# Interface.net
KiCad netlist of a schematic drawn in Altium Designer
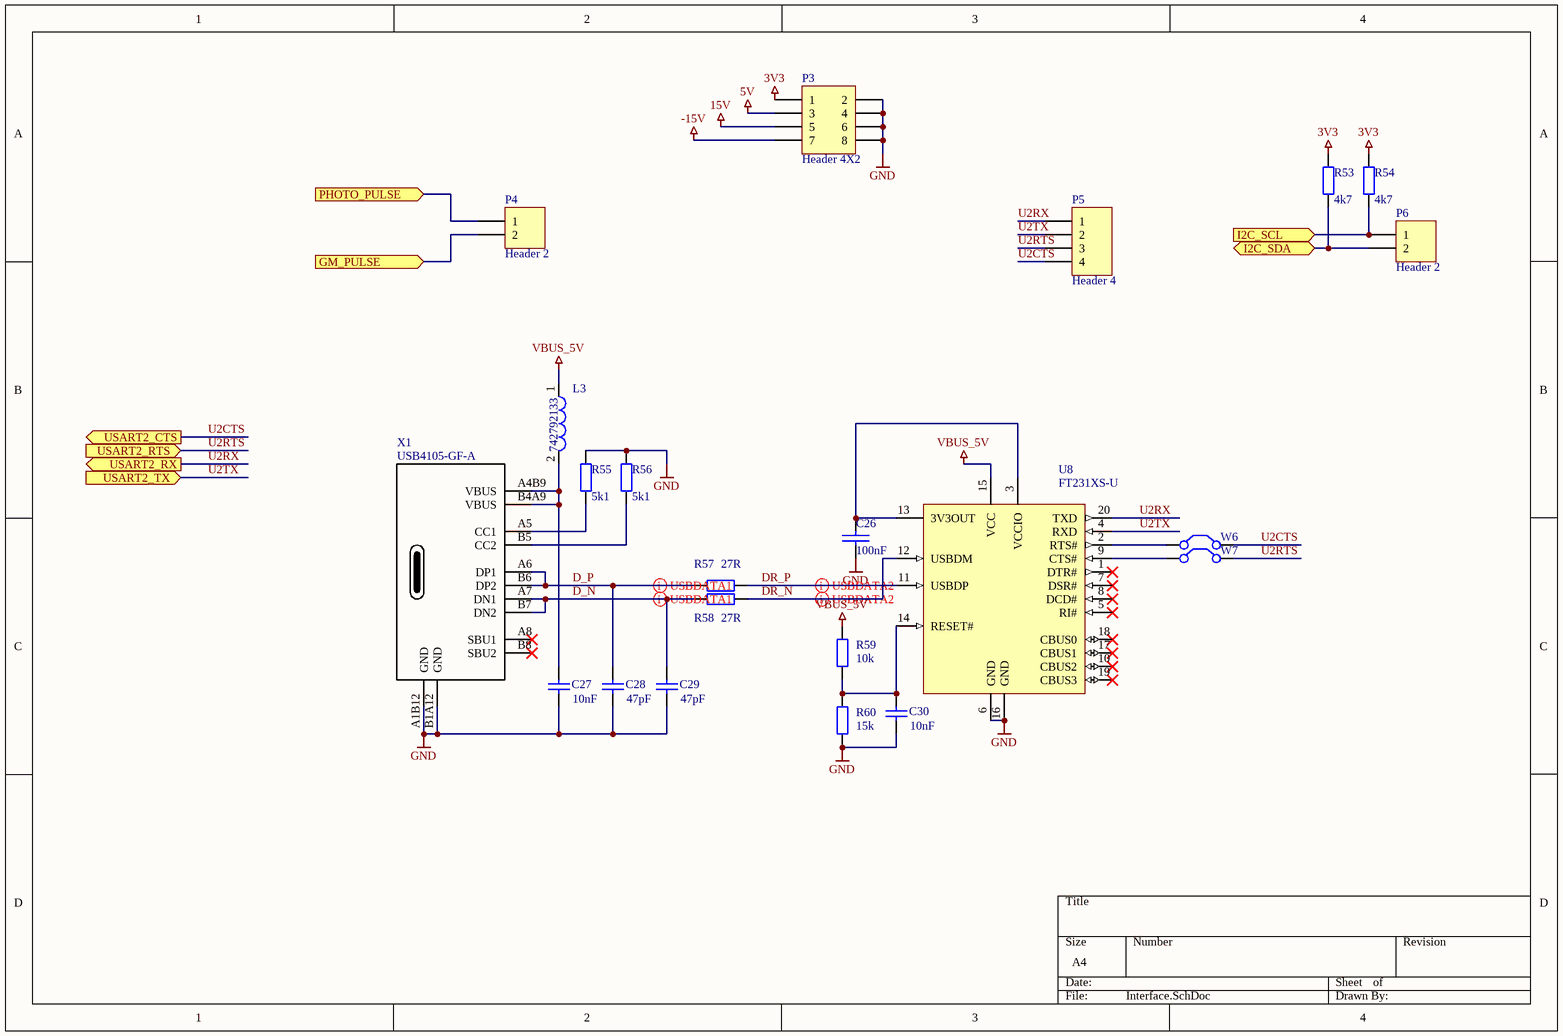
[diagram p0: Interface.SchDoc]

(export (version "E")
  (design (tool "Eeschema 10.0.6"))
  (components
    (comp (ref "C26") (value "100nF") (footprint "Cap_0805") (libsource (lib "*") (part "C")))
    (comp (ref "C27")
      (value "10nF")
      (footprint "6-0805_L")
      (description "Capacitor")
      (fields (field (name "PUBLISHER") "Altium Limited"))
      (libsource (lib "Miscellaneous Devices") (part "Cap"))
    )
    (comp (ref "C28")
      (value "47pF")
      (footprint "6-0805_L")
      (description "Capacitor")
      (fields (field (name "PUBLISHER") "Altium Limited"))
      (libsource (lib "Miscellaneous Devices") (part "Cap"))
    )
    (comp (ref "C29")
      (value "47pF")
      (footprint "6-0805_L")
      (description "Capacitor")
      (fields (field (name "PUBLISHER") "Altium Limited"))
      (libsource (lib "Miscellaneous Devices") (part "Cap"))
    )
    (comp (ref "C30")
      (value "10nF")
      (footprint "Cap_0805")
      (description "Capacitor")
      (fields (field (name "PUBLISHER") "Altium Limited"))
      (libsource (lib "Miscellaneous Devices") (part "Cap"))
    )
    (comp (ref "L3")
      (value "742792133")
      (footprint "SMD-1206")
      (description "SMD EMI Suppression Ferrite Bead WE-CBF, Z = 600 Ohm")
      (libsource (lib "Altium Content Vault") (part "PAS-IND-INDUCTOR-2"))
    )
    (comp (ref "P3")
      (value "Header 4X2")
      (footprint "HDR2X4")
      (description "Header, 4-Pin, Dual row")
      (fields (field (name "PUBLISHER") "Altium Limited"))
      (libsource (lib "Miscellaneous Connectors") (part "Header 4X2"))
    )
    (comp (ref "P4")
      (value "Header 2")
      (footprint "HDR1X2")
      (description "Header, 2-Pin")
      (fields (field (name "PUBLISHER") "Altium Limited"))
      (libsource (lib "Miscellaneous Connectors") (part "Header 2"))
    )
    (comp (ref "P5")
      (value "Header 4")
      (footprint "HDR1X4")
      (description "Header, 4-Pin")
      (fields (field (name "PUBLISHER") "Altium Limited"))
      (libsource (lib "Miscellaneous Connectors") (part "Header 4"))
    )
    (comp (ref "P6")
      (value "Header 2")
      (footprint "HDR1X2")
      (description "Header, 2-Pin")
      (fields (field (name "PUBLISHER") "Altium Limited"))
      (libsource (lib "Miscellaneous Connectors") (part "Header 2"))
    )
    (comp (ref "R53")
      (value "4k7")
      (footprint "RES_0805")
      (description "Res 0805")
      (fields (field (name "Comment") "5k1") (field (name "PUBLISHER") "Altium Limited"))
      (libsource (lib "Miscellaneous Devices") (part "Res2"))
    )
    (comp (ref "R54")
      (value "4k7")
      (footprint "RES_0805")
      (description "Res 0805")
      (fields (field (name "Comment") "5k1") (field (name "PUBLISHER") "Altium Limited"))
      (libsource (lib "Miscellaneous Devices") (part "Res2"))
    )
    (comp (ref "R55")
      (value "5k1")
      (footprint "RES_0805")
      (description "Res 0805")
      (fields (field (name "PUBLISHER") "Altium Limited"))
      (libsource (lib "Miscellaneous Devices") (part "Res2"))
    )
    (comp (ref "R56")
      (value "5k1")
      (footprint "RES_0805")
      (description "Res 0805")
      (fields (field (name "PUBLISHER") "Altium Limited"))
      (libsource (lib "Miscellaneous Devices") (part "Res2"))
    )
    (comp (ref "R57")
      (value "27R")
      (footprint "RES_0805")
      (description "Res 0805")
      (fields (field (name "PUBLISHER") "Altium Limited"))
      (libsource (lib "") (part "Res2_1"))
    )
    (comp (ref "R58")
      (value "27R")
      (footprint "RES_0805")
      (description "Res 0805")
      (fields (field (name "PUBLISHER") "Altium Limited"))
      (libsource (lib "") (part "Res2_1"))
    )
    (comp (ref "R59")
      (value "10k")
      (footprint "RES_0805")
      (description "Res 0805")
      (fields (field (name "PUBLISHER") "Altium Limited"))
      (libsource (lib "Miscellaneous Devices") (part "Res2"))
    )
    (comp (ref "R60")
      (value "15k")
      (footprint "RES_0805")
      (description "Res 0805")
      (fields (field (name "PUBLISHER") "Altium Limited"))
      (libsource (lib "Miscellaneous Devices") (part "Res2"))
    )
    (comp (ref "U8")
      (value "FT231XS-U")
      (footprint "SSOP-20_M")
      (fields (field (name "MANUFACTURER") "FTDI"))
      (libsource (lib "Altium Content Vault") (part "COM-USB-FT231XS-IL20"))
    )
    (comp (ref "W6")
      (value "Jumper")
      (footprint "JUMPER")
      (description "Jumper Wire")
      (fields (field (name "PUBLISHER") "Altium Limited"))
      (libsource (lib "Miscellaneous Devices") (part "Jumper"))
    )
    (comp (ref "W7")
      (value "Jumper")
      (footprint "JUMPER")
      (description "Jumper Wire")
      (fields (field (name "PUBLISHER") "Altium Limited"))
      (libsource (lib "Miscellaneous Devices") (part "Jumper"))
    )
    (comp (ref "X1")
      (value "USB4105-GF-A")
      (footprint "GCT_USB4105-GF-A")
      (description "USB4105-GF-A USB connector")
      (libsource (lib "2221-LIB") (part "USB-C Type 2.0"))
    )
  )
  (nets
    (net (code "1") (name "-15V") (class "Default")
      (node (ref "P3") (pin "7") (pinfunction "7_7") (pintype "passive"))
    )
    (net (code "2") (name "/DR_N") (class "Default")
      (node (ref "R58") (pin "2") (pinfunction "2_2") (pintype "passive"))
      (node (ref "U8") (pin "12") (pinfunction "USBDM_12") (pintype "input"))
    )
    (net (code "3") (name "/DR_P") (class "Default")
      (node (ref "R57") (pin "2") (pinfunction "2_2") (pintype "passive"))
      (node (ref "U8") (pin "11") (pinfunction "USBDP_11") (pintype "input"))
    )
    (net (code "4") (name "/D_N") (class "Default")
      (node (ref "C29") (pin "2") (pinfunction "2_2") (pintype "passive"))
      (node (ref "R58") (pin "1") (pinfunction "1_1") (pintype "passive"))
      (node (ref "X1") (pin "A7") (pinfunction "DN1_A7") (pintype "passive"))
      (node (ref "X1") (pin "B7") (pinfunction "DN2_B7") (pintype "passive"))
    )
    (net (code "5") (name "/D_P") (class "Default")
      (node (ref "C28") (pin "2") (pinfunction "2_2") (pintype "passive"))
      (node (ref "R57") (pin "1") (pinfunction "1_1") (pintype "passive"))
      (node (ref "X1") (pin "A6") (pinfunction "DP1_A6") (pintype "passive"))
      (node (ref "X1") (pin "B6") (pinfunction "DP2_B6") (pintype "passive"))
    )
    (net (code "6") (name "/GM_PULSE") (class "Default")
      (node (ref "P4") (pin "2") (pinfunction "2_2") (pintype "passive"))
    )
    (net (code "7") (name "/I2C_SCL") (class "Default")
      (node (ref "P6") (pin "1") (pinfunction "1_1") (pintype "passive"))
      (node (ref "R54") (pin "1") (pinfunction "1_1") (pintype "passive"))
    )
    (net (code "8") (name "/I2C_SDA") (class "Default")
      (node (ref "P6") (pin "2") (pinfunction "2_2") (pintype "passive"))
      (node (ref "R53") (pin "1") (pinfunction "1_1") (pintype "passive"))
    )
    (net (code "9") (name "/PHOTO_PULSE") (class "Default")
      (node (ref "P4") (pin "1") (pinfunction "1_1") (pintype "passive"))
    )
    (net (code "10") (name "/U2CTS") (class "Default")
      (node (ref "P5") (pin "4") (pinfunction "4_4") (pintype "passive"))
      (node (ref "W6") (pin "2") (pinfunction "C2_2") (pintype "passive"))
    )
    (net (code "11") (name "/U2RTS") (class "Default")
      (node (ref "P5") (pin "3") (pinfunction "3_3") (pintype "passive"))
      (node (ref "W7") (pin "2") (pinfunction "C2_2") (pintype "passive"))
    )
    (net (code "12") (name "/U2RX") (class "Default")
      (node (ref "P5") (pin "1") (pinfunction "1_1") (pintype "passive"))
      (node (ref "U8") (pin "20") (pinfunction "TXD_20") (pintype "output"))
    )
    (net (code "13") (name "/U2TX") (class "Default")
      (node (ref "P5") (pin "2") (pinfunction "2_2") (pintype "passive"))
      (node (ref "U8") (pin "4") (pinfunction "RXD_4") (pintype "input"))
    )
    (net (code "14") (name "3V3") (class "Default")
      (node (ref "P3") (pin "1") (pinfunction "1_1") (pintype "passive"))
      (node (ref "R53") (pin "2") (pinfunction "2_2") (pintype "passive"))
      (node (ref "R54") (pin "2") (pinfunction "2_2") (pintype "passive"))
    )
    (net (code "15") (name "5V") (class "Default")
      (node (ref "P3") (pin "3") (pinfunction "3_3") (pintype "passive"))
    )
    (net (code "16") (name "15V") (class "Default")
      (node (ref "P3") (pin "5") (pinfunction "5_5") (pintype "passive"))
    )
    (net (code "17") (name "GND") (class "Default")
      (node (ref "C26") (pin "2") (pinfunction "2_2") (pintype "passive"))
      (node (ref "C27") (pin "1") (pinfunction "1_1") (pintype "passive"))
      (node (ref "C28") (pin "1") (pinfunction "1_1") (pintype "passive"))
      (node (ref "C29") (pin "1") (pinfunction "1_1") (pintype "passive"))
      (node (ref "C30") (pin "1") (pinfunction "1_1") (pintype "passive"))
      (node (ref "P3") (pin "2") (pinfunction "2_2") (pintype "passive"))
      (node (ref "P3") (pin "4") (pinfunction "4_4") (pintype "passive"))
      (node (ref "P3") (pin "6") (pinfunction "6_6") (pintype "passive"))
      (node (ref "P3") (pin "8") (pinfunction "8_8") (pintype "passive"))
      (node (ref "R55") (pin "2") (pinfunction "2_2") (pintype "passive"))
      (node (ref "R56") (pin "2") (pinfunction "2_2") (pintype "passive"))
      (node (ref "R60") (pin "1") (pinfunction "1_1") (pintype "passive"))
      (node (ref "U8") (pin "16") (pinfunction "GND_16") (pintype "power_in"))
      (node (ref "U8") (pin "6") (pinfunction "GND_6") (pintype "power_in"))
      (node (ref "X1") (pin "A1B12") (pinfunction "GND_A1B12") (pintype "passive"))
      (node (ref "X1") (pin "B1A12") (pinfunction "GND_B1A12") (pintype "passive"))
    )
    (net (code "18") (name "Net-(C27-Pad2)") (class "Default")
      (node (ref "C27") (pin "2") (pinfunction "2_2") (pintype "passive"))
      (node (ref "L3") (pin "2") (pinfunction "2_2") (pintype "passive"))
      (node (ref "X1") (pin "A4B9") (pinfunction "VBUS_A4B9") (pintype "passive"))
      (node (ref "X1") (pin "B4A9") (pinfunction "VBUS_B4A9") (pintype "passive"))
    )
    (net (code "19") (name "Net-(U8-3V3OUT)") (class "Default")
      (node (ref "C26") (pin "1") (pinfunction "1_1") (pintype "passive"))
      (node (ref "U8") (pin "13") (pinfunction "3V3OUT_13") (pintype "power_in"))
      (node (ref "U8") (pin "3") (pinfunction "VCCIO_3") (pintype "power_in"))
    )
    (net (code "20") (name "Net-(U8-CTS#)") (class "Default")
      (node (ref "U8") (pin "9") (pinfunction "CTS#_9") (pintype "input"))
      (node (ref "W7") (pin "1") (pinfunction "C1_1") (pintype "passive"))
    )
    (net (code "21") (name "Net-(U8-RESET#)") (class "Default")
      (node (ref "C30") (pin "2") (pinfunction "2_2") (pintype "passive"))
      (node (ref "R59") (pin "1") (pinfunction "1_1") (pintype "passive"))
      (node (ref "R60") (pin "2") (pinfunction "2_2") (pintype "passive"))
      (node (ref "U8") (pin "14") (pinfunction "RESET#_14") (pintype "input"))
    )
    (net (code "22") (name "Net-(U8-RTS#)") (class "Default")
      (node (ref "U8") (pin "2") (pinfunction "RTS#_2") (pintype "output"))
      (node (ref "W6") (pin "1") (pinfunction "C1_1") (pintype "passive"))
    )
    (net (code "23") (name "Net-(X1-CC1)") (class "Default")
      (node (ref "R55") (pin "1") (pinfunction "1_1") (pintype "passive"))
      (node (ref "X1") (pin "A5") (pinfunction "CC1_A5") (pintype "passive"))
    )
    (net (code "24") (name "Net-(X1-CC2)") (class "Default")
      (node (ref "R56") (pin "1") (pinfunction "1_1") (pintype "passive"))
      (node (ref "X1") (pin "B5") (pinfunction "CC2_B5") (pintype "passive"))
    )
    (net (code "25") (name "VBUS_5V") (class "Default")
      (node (ref "L3") (pin "1") (pinfunction "1_1") (pintype "passive"))
      (node (ref "R59") (pin "2") (pinfunction "2_2") (pintype "passive"))
      (node (ref "U8") (pin "15") (pinfunction "VCC_15") (pintype "power_in"))
    )
    (net (code "26") (name "unconnected-(U8-CBUS0-Pad18)") (class "Default")
      (node (ref "U8") (pin "18") (pinfunction "CBUS0_18") (pintype "bidirectional+no_connect"))
    )
    (net (code "27") (name "unconnected-(U8-CBUS1-Pad17)") (class "Default")
      (node (ref "U8") (pin "17") (pinfunction "CBUS1_17") (pintype "bidirectional+no_connect"))
    )
    (net (code "28") (name "unconnected-(U8-CBUS2-Pad10)") (class "Default")
      (node (ref "U8") (pin "10") (pinfunction "CBUS2_10") (pintype "bidirectional+no_connect"))
    )
    (net (code "29") (name "unconnected-(U8-CBUS3-Pad19)") (class "Default")
      (node (ref "U8") (pin "19") (pinfunction "CBUS3_19") (pintype "bidirectional+no_connect"))
    )
    (net (code "30") (name "unconnected-(U8-DCD#-Pad8)") (class "Default")
      (node (ref "U8") (pin "8") (pinfunction "DCD#_8") (pintype "input+no_connect"))
    )
    (net (code "31") (name "unconnected-(U8-DSR#-Pad7)") (class "Default")
      (node (ref "U8") (pin "7") (pinfunction "DSR#_7") (pintype "input+no_connect"))
    )
    (net (code "32") (name "unconnected-(U8-DTR#-Pad1)") (class "Default")
      (node (ref "U8") (pin "1") (pinfunction "DTR#_1") (pintype "output+no_connect"))
    )
    (net (code "33") (name "unconnected-(U8-RI#-Pad5)") (class "Default")
      (node (ref "U8") (pin "5") (pinfunction "RI#_5") (pintype "input+no_connect"))
    )
    (net (code "34") (name "unconnected-(X1-SBU1-PadA8)") (class "Default")
      (node (ref "X1") (pin "A8") (pinfunction "SBU1_A8") (pintype "passive+no_connect"))
    )
    (net (code "35") (name "unconnected-(X1-SBU2-PadB8)") (class "Default")
      (node (ref "X1") (pin "B8") (pinfunction "SBU2_B8") (pintype "passive+no_connect"))
    )
  )
)
